# Brd_4_Sensor_Shield_Kevin_Tom.net
KiCad netlist of a schematic drawn in Altium Designer
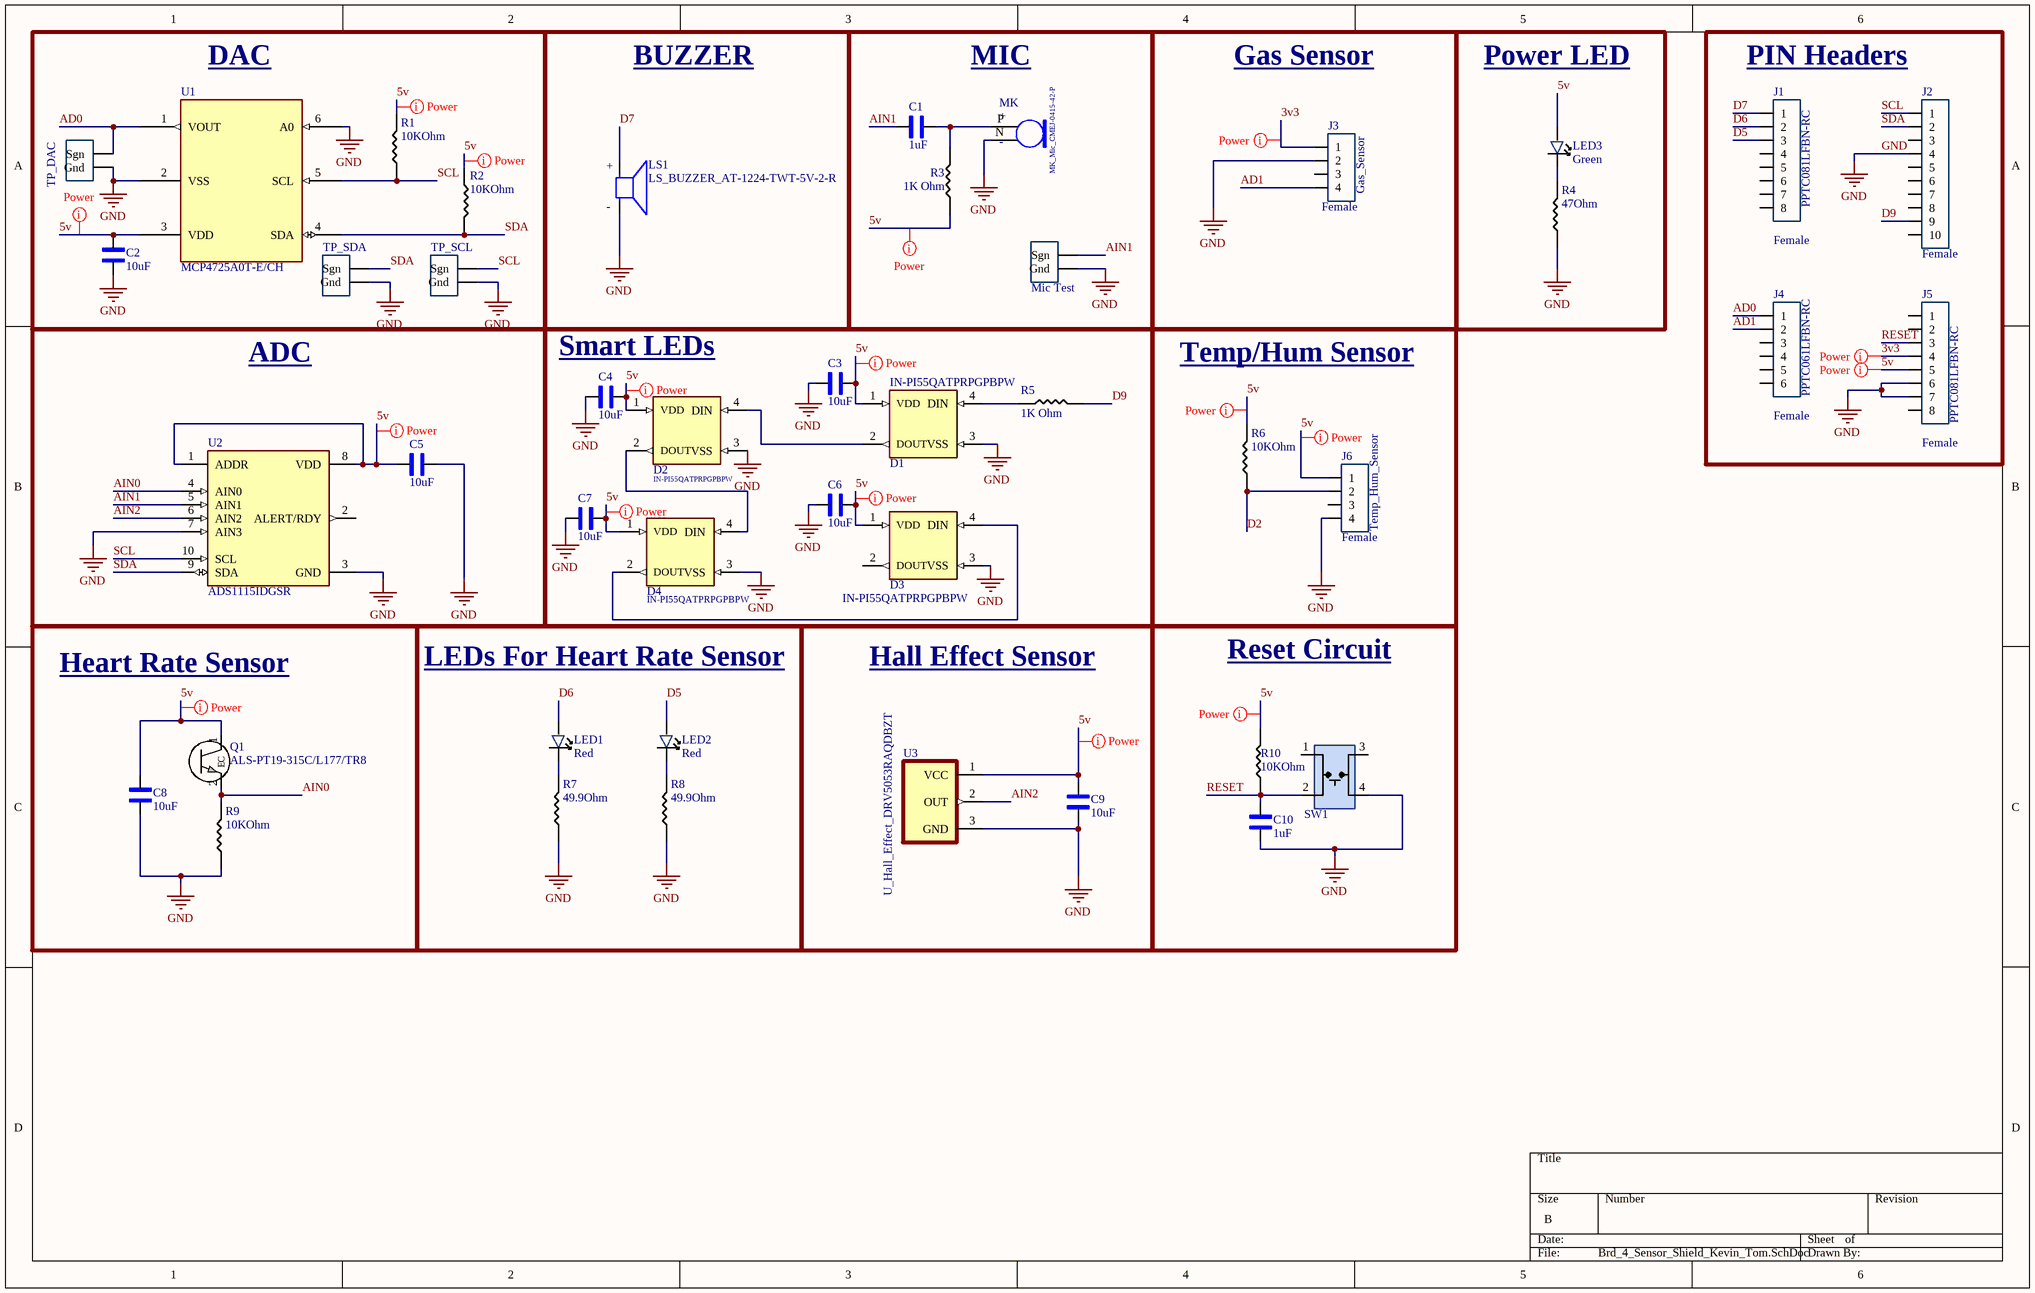
[diagram p0: Brd_4_Sensor_Shield_Kevin_Tom.SchDoc]

(export (version "E")
  (design (tool "Eeschema 10.0.6"))
  (components
    (comp (ref "C1")
      (value "1uF")
      (footprint "1206_Passive_Capacitor")
      (description "MULTILAYER CERAMIC CAPACITORS MLCC - SMD/SMT 1UF 50V 1206 ROHS")
      (fields (field (name "DIGIKEY PART") "399-8150-1-ND") (field (name "MFR PART #") "CL31B105KBHNNNE"))
      (libsource (lib "ECEN5730Lib_JLC_2021_08") (part "C_1uF_1206"))
    )
    (comp (ref "C2")
      (value "10uF")
      (footprint "1206_Passive_Capacitor")
      (description "10uF ±10% 50V X5R 1206 Multilayer Ceramic Capacitors MLCC - SMD/SMT RoHS")
      (fields (field (name "LCSC PART#") "C13585") (field (name "MFR PART #") "CL31A106KBHNNNE"))
      (libsource (lib "ECEN5730Lib_JLC_2021_08") (part "C_10uF_1206"))
    )
    (comp (ref "C3")
      (value "10uF")
      (footprint "1206_Passive_Capacitor")
      (description "10uF ±10% 50V X5R 1206 Multilayer Ceramic Capacitors MLCC - SMD/SMT RoHS")
      (fields (field (name "LCSC PART#") "C13585") (field (name "MFR PART #") "CL31A106KBHNNNE"))
      (libsource (lib "ECEN5730Lib_JLC_2021_08") (part "C_10uF_1206"))
    )
    (comp (ref "C4")
      (value "10uF")
      (footprint "1206_Passive_Capacitor")
      (description "10uF ±10% 50V X5R 1206 Multilayer Ceramic Capacitors MLCC - SMD/SMT RoHS")
      (fields (field (name "LCSC PART#") "C13585") (field (name "MFR PART #") "CL31A106KBHNNNE"))
      (libsource (lib "ECEN5730Lib_JLC_2021_08") (part "C_10uF_1206"))
    )
    (comp (ref "C5")
      (value "10uF")
      (footprint "1206_Passive_Capacitor")
      (description "10uF ±10% 50V X5R 1206 Multilayer Ceramic Capacitors MLCC - SMD/SMT RoHS")
      (fields (field (name "LCSC PART#") "C13585") (field (name "MFR PART #") "CL31A106KBHNNNE"))
      (libsource (lib "ECEN5730Lib_JLC_2021_08") (part "C_10uF_1206"))
    )
    (comp (ref "C6")
      (value "10uF")
      (footprint "1206_Passive_Capacitor")
      (description "10uF ±10% 50V X5R 1206 Multilayer Ceramic Capacitors MLCC - SMD/SMT RoHS")
      (fields (field (name "LCSC PART#") "C13585") (field (name "MFR PART #") "CL31A106KBHNNNE"))
      (libsource (lib "ECEN5730Lib_JLC_2021_08") (part "C_10uF_1206"))
    )
    (comp (ref "C7")
      (value "10uF")
      (footprint "1206_Passive_Capacitor")
      (description "10uF ±10% 50V X5R 1206 Multilayer Ceramic Capacitors MLCC - SMD/SMT RoHS")
      (fields (field (name "LCSC PART#") "C13585") (field (name "MFR PART #") "CL31A106KBHNNNE"))
      (libsource (lib "ECEN5730Lib_JLC_2021_08") (part "C_10uF_1206"))
    )
    (comp (ref "C8")
      (value "10uF")
      (footprint "1206_Passive_Capacitor")
      (description "10uF ±10% 50V X5R 1206 Multilayer Ceramic Capacitors MLCC - SMD/SMT RoHS")
      (fields (field (name "LCSC PART#") "C13585") (field (name "MFR PART #") "CL31A106KBHNNNE"))
      (libsource (lib "ECEN5730Lib_JLC_2021_08") (part "C_10uF_1206"))
    )
    (comp (ref "C9")
      (value "10uF")
      (footprint "1206_Passive_Capacitor")
      (description "10uF ±10% 50V X5R 1206 Multilayer Ceramic Capacitors MLCC - SMD/SMT RoHS")
      (fields (field (name "LCSC PART#") "C13585") (field (name "MFR PART #") "CL31A106KBHNNNE"))
      (libsource (lib "ECEN5730Lib_JLC_2021_08") (part "C_10uF_1206"))
    )
    (comp (ref "C10")
      (value "1uF")
      (footprint "1206_Passive_Capacitor")
      (description "MULTILAYER CERAMIC CAPACITORS MLCC - SMD/SMT 1UF 50V 1206 ROHS")
      (fields (field (name "DIGIKEY PART") "399-8150-1-ND") (field (name "MFR PART #") "CL31B105KBHNNNE"))
      (libsource (lib "ECEN5730Lib_JLC_2021_08") (part "C_1uF_1206"))
    )
    (comp (ref "D1")
      (value "IN-PI55QATPRPGPBPW")
      (footprint "SERIAL_LED")
      (description "Digital Series Cascade LED")
      (libsource (lib "ECEN5730Lib_Manual_2021_08") (part "LED_Smart_5050"))
    )
    (comp (ref "D2")
      (value "IN-PI55QATPRPGPBPW")
      (footprint "SERIAL_LED")
      (description "Digital Series Cascade LED")
      (libsource (lib "ECEN5730Lib_Manual_2021_08") (part "LED_Smart_5050"))
    )
    (comp (ref "D3")
      (value "IN-PI55QATPRPGPBPW")
      (footprint "SERIAL_LED")
      (description "Digital Series Cascade LED")
      (libsource (lib "ECEN5730Lib_Manual_2021_08") (part "LED_Smart_5050"))
    )
    (comp (ref "D4")
      (value "IN-PI55QATPRPGPBPW")
      (footprint "SERIAL_LED")
      (description "Digital Series Cascade LED")
      (libsource (lib "ECEN5730Lib_Manual_2021_08") (part "LED_Smart_5050"))
    )
    (comp (ref "J1")
      (value "PPTC081LFBN-RC")
      (footprint "8_PIN_ARDUINO_100MIL")
      (description "8 Position Header Connector 0.100\" (2.54mm) Through Hole Tin")
      (fields
        (field (name "DIGIKEY PART") "S7006-ND")
        (field (name "LCSC PART#") "C27438")
        (field (name "ALTIUM_VALUE") "Female")
      )
      (libsource (lib "ECEN5730Lib_JLC_2021_08") (part "JF_8_PIN_FEMALE_ARDUINO"))
    )
    (comp (ref "J2")
      (value "Female")
      (footprint "10_PIN_ARDUINO_100MIL")
      (description "10 Position Header Connector 0.100\" (2.54mm) Through Hole Tin")
      (fields (field (name "DIGIKEY PART") "S7008-ND") (field (name "LCSC PART#") "C225507"))
      (libsource (lib "ECEN5730Lib_JLC_2021_08") (part "JF_10_PIN_FEMALE_ARDUINO"))
    )
    (comp (ref "J3")
      (value "Gas_Sensor")
      (footprint "4_PIN_100MIL")
      (description "4 Position Header Connector 0.100\" (2.54mm) Through Hole Tin")
      (fields
        (field (name "DIGIKEY PART") "S7004-ND")
        (field (name "LCSC PART#") "C40877")
        (field (name "ALTIUM_VALUE") "Female")
      )
      (libsource (lib "keto_Sensor_lib_27-03") (part "JF_4_PIN_FEMALE_ARDUINO"))
    )
    (comp (ref "J4")
      (value "PPTC061LFBN-RC")
      (footprint "6_PIN_ARDUINO_100mil")
      (description "6 Position Header Connector 0.100\" (2.54mm) Through Hole Tin")
      (fields
        (field (name "DIGIKEY PART") "S7004-ND")
        (field (name "LCSC PART#") "C40877")
        (field (name "ALTIUM_VALUE") "Female")
      )
      (libsource (lib "ECEN5730Lib_JLC_2021_08") (part "JF_6_PIN_FEMALE_ARDUINO"))
    )
    (comp (ref "J5")
      (value "PPTC081LFBN-RC")
      (footprint "8_PIN_ARDUINO_100MIL")
      (description "8 Position Header Connector 0.100\" (2.54mm) Through Hole Tin")
      (fields
        (field (name "DIGIKEY PART") "S7006-ND")
        (field (name "LCSC PART#") "C27438")
        (field (name "ALTIUM_VALUE") "Female")
      )
      (libsource (lib "ECEN5730Lib_JLC_2021_08") (part "JF_8_PIN_FEMALE_ARDUINO"))
    )
    (comp (ref "J6")
      (value "Temp_Hum_Sensor")
      (footprint "4_PIN_100MIL")
      (description "4 Position Header Connector 0.100\" (2.54mm) Through Hole Tin")
      (fields
        (field (name "DIGIKEY PART") "S7004-ND")
        (field (name "LCSC PART#") "C40877")
        (field (name "ALTIUM_VALUE") "Female")
      )
      (libsource (lib "keto_Sensor_lib_27-03") (part "JF_4_PIN_FEMALE_ARDUINO"))
    )
    (comp (ref "LED1")
      (value "Red")
      (footprint "LED_1206")
      (description "Red 621~631nm 1206 Light Emitting Diodes (LED) RoHS")
      (fields (field (name "MFR PART #") "15-21/R6C-FQ1R1B/2T") (field (name "LCSC PART#") "C93133"))
      (libsource (lib "ECEN5730Lib_JLC_2021_08") (part "LED_RED_1206"))
    )
    (comp (ref "LED2")
      (value "Red")
      (footprint "LED_1206")
      (description "Red 621~631nm 1206 Light Emitting Diodes (LED) RoHS")
      (fields (field (name "MFR PART #") "15-21/R6C-FQ1R1B/2T") (field (name "LCSC PART#") "C93133"))
      (libsource (lib "ECEN5730Lib_JLC_2021_08") (part "LED_RED_1206"))
    )
    (comp (ref "LED3")
      (value "Green")
      (footprint "LED_1206")
      (description "Green 513~528nm 1206 Light Emitting Diodes (LED) RoHS")
      (fields (field (name "MFR PART #") "SZYY1206G") (field (name "LCSC PART#") "C434439"))
      (libsource (lib "ECEN5730Lib_JLC_2021_08") (part "LED_GREEN_1206"))
    )
    (comp (ref "LS1")
      (value "LS_BUZZER_AT-1224-TWT-5V-2-R")
      (footprint "XDCR_AT-1224-TWT-5V-2-R")
      (description "AUDIO TRANSDUCER 5 VP-P 87 DB 2400 HZ")
      (fields (field (name "MF") "PUI Audio,") (field (name "MP") "AT-1224-TWT-5V-2-R"))
      (libsource (lib "keto_Sensor_lib_27-03") (part "LS_BUZZER_AT-1224-TWT-5V-2-R"))
    )
    (comp (ref "Mic Test")
      (value "10x Probe TP")
      (footprint "TP10x_Probe")
      (description "Test Point 300 mil centers")
      (libsource (lib "ECEN5730Lib_Manual_2021_08") (part "TP_10x_Probe"))
    )
    (comp (ref "MK")
      (value "MK_Mic_CMEJ-0415-42-P")
      (footprint "MK_MIC_CMEJ-0415-42-P")
      (description "0.4mm OMNIDIRECTIONAL MIC")
      (fields (field (name "MF") "CUI Devices") (field (name "DIGI-KEY_PART_NUMBER") "102-6542-ND"))
      (libsource (lib "keto_Sensor_lib_27-03") (part "MK_Mic_CMEJ-0415-42-P"))
    )
    (comp (ref "Q1")
      (value "ALS-PT19-315C/L177/TR8")
      (footprint "LED_77/TR8_EVE")
      (description "Ambient Light Sensor")
      (fields (field (name "LCSC PART#") "C146233"))
      (libsource (lib "ECEN5730Lib_JLC_2021_08") (part "Q_Phototransistor"))
    )
    (comp (ref "R1")
      (value "10KOhm")
      (footprint "1206_Passive_Resitor")
      (description "10 kOhms ±5% 0.25W, 1/4W Chip Resistor 1206 (3216 Metric) Automotive AEC-Q200 Thick Film")
      (fields (field (name "DIGIKEY PART") "RMCF1206JT300RCT-ND") (field (name "LCSC PART#") "C17902"))
      (libsource (lib "ECEN5730Lib_JLC_2021_08") (part "R_10KOhm_1206"))
    )
    (comp (ref "R2")
      (value "10KOhm")
      (footprint "1206_Passive_Resitor")
      (description "10 kOhms ±5% 0.25W, 1/4W Chip Resistor 1206 (3216 Metric) Automotive AEC-Q200 Thick Film")
      (fields (field (name "DIGIKEY PART") "RMCF1206JT300RCT-ND") (field (name "LCSC PART#") "C17902"))
      (libsource (lib "ECEN5730Lib_JLC_2021_08") (part "R_10KOhm_1206"))
    )
    (comp (ref "R3")
      (value "1K Ohm")
      (footprint "1206_Passive_Resitor")
      (description "CHIP RESISTOR - SURFACE MOUNT 1KOHMS ±1% 1/4W 1206 ROHS")
      (fields (field (name "DIGIKEY PART") "RNCP1206FTD1K00CT-ND") (field (name "LCSC PART#") "C4410"))
      (libsource (lib "ECEN5730Lib_JLC_2021_08") (part "R_1K_1206"))
    )
    (comp (ref "R4")
      (value "47Ohm")
      (footprint "1206_Passive_Resitor")
      (description "47Ω ±5% 0.25W ±200ppm/℃ 1206 Chip Resistor - Surface Mount RoHS")
      (fields (field (name "MFR PART #") "1206W4J0470T5E") (field (name "LCSC PART#") "C25384"))
      (libsource (lib "ECEN5730Lib_JLC_2021_08") (part "R_47Ohm_1206"))
    )
    (comp (ref "R5")
      (value "1K Ohm")
      (footprint "1206_Passive_Resitor")
      (description "CHIP RESISTOR - SURFACE MOUNT 1KOHMS ±1% 1/4W 1206 ROHS")
      (fields (field (name "DIGIKEY PART") "RNCP1206FTD1K00CT-ND") (field (name "LCSC PART#") "C4410"))
      (libsource (lib "ECEN5730Lib_JLC_2021_08") (part "R_1K_1206"))
    )
    (comp (ref "R6")
      (value "10KOhm")
      (footprint "1206_Passive_Resitor")
      (description "10 kOhms ±5% 0.25W, 1/4W Chip Resistor 1206 (3216 Metric) Automotive AEC-Q200 Thick Film")
      (fields (field (name "DIGIKEY PART") "RMCF1206JT300RCT-ND") (field (name "LCSC PART#") "C17902"))
      (libsource (lib "ECEN5730Lib_JLC_2021_08") (part "R_10KOhm_1206"))
    )
    (comp (ref "R7")
      (value "49.9Ohm")
      (footprint "0402_Passive_Resistor")
      (description "CHIP RESISTOR - SURFACE MOUNT 49.9OHMS ±1% 1/16W 0402 ROHS")
      (fields (field (name "MFR PART #") "0402WGF499JTCE") (field (name "LCSC PART#") "C25120"))
      (libsource (lib "ECEN5730Lib_JLC_2021_08") (part "R_50Ohm_0402"))
    )
    (comp (ref "R8")
      (value "49.9Ohm")
      (footprint "0402_Passive_Resistor")
      (description "CHIP RESISTOR - SURFACE MOUNT 49.9OHMS ±1% 1/16W 0402 ROHS")
      (fields (field (name "MFR PART #") "0402WGF499JTCE") (field (name "LCSC PART#") "C25120"))
      (libsource (lib "ECEN5730Lib_JLC_2021_08") (part "R_50Ohm_0402"))
    )
    (comp (ref "R9")
      (value "10KOhm")
      (footprint "1206_Passive_Resitor")
      (description "10 kOhms ±5% 0.25W, 1/4W Chip Resistor 1206 (3216 Metric) Automotive AEC-Q200 Thick Film")
      (fields (field (name "DIGIKEY PART") "RMCF1206JT300RCT-ND") (field (name "LCSC PART#") "C17902"))
      (libsource (lib "ECEN5730Lib_JLC_2021_08") (part "R_10KOhm_1206"))
    )
    (comp (ref "R10")
      (value "10KOhm")
      (footprint "1206_Passive_Resitor")
      (description "10 kOhms ±5% 0.25W, 1/4W Chip Resistor 1206 (3216 Metric) Automotive AEC-Q200 Thick Film")
      (fields (field (name "DIGIKEY PART") "RMCF1206JT300RCT-ND") (field (name "LCSC PART#") "C17902"))
      (libsource (lib "ECEN5730Lib_JLC_2021_08") (part "R_10KOhm_1206"))
    )
    (comp (ref "SW1")
      (value "TL3305AF160QG")
      (footprint "Switch_JLC")
      (description "Tactile Switch SPST-NO Top Actuated Surface Mount")
      (fields (field (name "MFR PART #") "C174049"))
      (libsource (lib "ECEN5730Lib_JLC_2021_08") (part "SW_Push_Button_JLC"))
    )
    (comp (ref "TP2")
      (value "TP_DAC")
      (footprint "TP10x_Probe")
      (description "Test Point 300 mil centers")
      (libsource (lib "ECEN5730Lib_Manual_2021_08") (part "TP_10x_Probe"))
    )
    (comp (ref "TP3")
      (value "TP_SDA")
      (footprint "TP10x_Probe")
      (description "Test Point 300 mil centers")
      (libsource (lib "ECEN5730Lib_Manual_2021_08") (part "TP_10x_Probe"))
    )
    (comp (ref "TP4")
      (value "TP_SCL")
      (footprint "TP10x_Probe")
      (description "Test Point 300 mil centers")
      (libsource (lib "ECEN5730Lib_Manual_2021_08") (part "TP_10x_Probe"))
    )
    (comp (ref "U1")
      (value "MCP4725A0T-E/CH")
      (footprint "DAC_MCP4725A0T-E/CH")
      (description "Voltage-Buffered 12 1 I2C SOT-23-6 Digital To Analog Converters (DACs) ROHS")
      (fields (field (name "LCSC PART#") "C144198"))
      (libsource (lib "keto_Sensor_lib_27-03") (part "U_DAC_MCP4725A0T-E/CH"))
    )
    (comp (ref "U2")
      (value "ADS1115IDGSR")
      (footprint "ADC_ADS1115IDGSR")
      (description "16-Bit ADC with Integrated MUX, PGA, Comparator, Oscillator, and Reference 10-VSSOP -40 to 125")
      (fields (field (name "LCSC PART#") "C37593"))
      (libsource (lib "ECEN5730Lib_JLC_2021_08") (part "U_ADC_ADS1115IDGSR"))
    )
    (comp (ref "U3")
      (value "U_Hall_Effect_DRV5053RAQDBZT")
      (footprint "U_Hall_Effect_SOT95P237X112-3N")
      (description "SENSOR LINEAR ANALOG SOT23-3")
      (fields (field (name "MFR PART #") "DRV5053RAQDBZT"))
      (libsource (lib "keto_Sensor_lib_27-03") (part "U_Hall_Effect_DRV5053RAQDBZT"))
    )
  )
  (nets
    (net (code "1") (name "/3v3") (class "Default")
      (node (ref "J3") (pin "1") (pinfunction "1_1") (pintype "passive"))
      (node (ref "J5") (pin "4") (pinfunction "4_4") (pintype "passive"))
    )
    (net (code "2") (name "/5v") (class "Default")
      (node (ref "C2") (pin "2") (pinfunction "2_2") (pintype "passive"))
      (node (ref "C3") (pin "1") (pinfunction "1_1") (pintype "passive"))
      (node (ref "C4") (pin "1") (pinfunction "1_1") (pintype "passive"))
      (node (ref "C5") (pin "2") (pinfunction "2_2") (pintype "passive"))
      (node (ref "C6") (pin "1") (pinfunction "1_1") (pintype "passive"))
      (node (ref "C7") (pin "1") (pinfunction "1_1") (pintype "passive"))
      (node (ref "C8") (pin "1") (pinfunction "1_1") (pintype "passive"))
      (node (ref "C9") (pin "1") (pinfunction "1_1") (pintype "passive"))
      (node (ref "D1") (pin "1") (pinfunction "VDD_1") (pintype "input"))
      (node (ref "D2") (pin "1") (pinfunction "VDD_1") (pintype "input"))
      (node (ref "D3") (pin "1") (pinfunction "VDD_1") (pintype "input"))
      (node (ref "D4") (pin "1") (pinfunction "VDD_1") (pintype "input"))
      (node (ref "J5") (pin "5") (pinfunction "5_5") (pintype "passive"))
      (node (ref "J6") (pin "1") (pinfunction "1_1") (pintype "passive"))
      (node (ref "LED3") (pin "1") (pinfunction "1_1") (pintype "passive"))
      (node (ref "Q1") (pin "1") (pinfunction "C_1") (pintype "passive"))
      (node (ref "R1") (pin "2") (pinfunction "2_2") (pintype "passive"))
      (node (ref "R10") (pin "2") (pinfunction "2_2") (pintype "passive"))
      (node (ref "R2") (pin "1") (pinfunction "1_1") (pintype "passive"))
      (node (ref "R3") (pin "1") (pinfunction "1_1") (pintype "passive"))
      (node (ref "R6") (pin "2") (pinfunction "2_2") (pintype "passive"))
      (node (ref "U1") (pin "3") (pinfunction "VDD_3") (pintype "power_in"))
      (node (ref "U2") (pin "1") (pinfunction "ADDR_1") (pintype "passive"))
      (node (ref "U2") (pin "8") (pinfunction "VDD_8") (pintype "power_in"))
      (node (ref "U3") (pin "1") (pinfunction "VCC_1") (pintype "power_in"))
    )
    (net (code "3") (name "/AD0") (class "Default")
      (node (ref "J4") (pin "1") (pinfunction "1_1") (pintype "passive"))
      (node (ref "TP2") (pin "1") (pinfunction "Sgn_1") (pintype "passive"))
      (node (ref "U1") (pin "1") (pinfunction "VOUT_1") (pintype "output"))
    )
    (net (code "4") (name "/AD1") (class "Default")
      (node (ref "J3") (pin "4") (pinfunction "4_4") (pintype "passive"))
      (node (ref "J4") (pin "2") (pinfunction "2_2") (pintype "passive"))
    )
    (net (code "5") (name "/AIN0") (class "Default")
      (node (ref "Q1") (pin "2") (pinfunction "E_2") (pintype "passive"))
      (node (ref "R9") (pin "2") (pinfunction "2_2") (pintype "passive"))
      (node (ref "U2") (pin "4") (pinfunction "AIN0_4") (pintype "input"))
    )
    (net (code "6") (name "/AIN1") (class "Default")
      (node (ref "C1") (pin "1") (pinfunction "1_1") (pintype "passive"))
      (node (ref "Mic Test") (pin "1") (pinfunction "Sgn_1") (pintype "passive"))
      (node (ref "U2") (pin "5") (pinfunction "AIN1_5") (pintype "input"))
    )
    (net (code "7") (name "/AIN2") (class "Default")
      (node (ref "U2") (pin "6") (pinfunction "AIN2_6") (pintype "input"))
      (node (ref "U3") (pin "2") (pinfunction "OUT_2") (pintype "output"))
    )
    (net (code "8") (name "/D2") (class "Default")
      (node (ref "J6") (pin "2") (pinfunction "2_2") (pintype "passive"))
      (node (ref "R6") (pin "1") (pinfunction "1_1") (pintype "passive"))
    )
    (net (code "9") (name "/D5") (class "Default")
      (node (ref "J1") (pin "3") (pinfunction "3_3") (pintype "passive"))
      (node (ref "LED2") (pin "1") (pinfunction "1_1") (pintype "passive"))
    )
    (net (code "10") (name "/D6") (class "Default")
      (node (ref "J1") (pin "2") (pinfunction "2_2") (pintype "passive"))
      (node (ref "LED1") (pin "1") (pinfunction "1_1") (pintype "passive"))
    )
    (net (code "11") (name "/D7") (class "Default")
      (node (ref "J1") (pin "1") (pinfunction "1_1") (pintype "passive"))
      (node (ref "LS1") (pin "P") (pinfunction "P_P") (pintype "passive"))
    )
    (net (code "12") (name "/D9") (class "Default")
      (node (ref "J2") (pin "9") (pinfunction "9_9") (pintype "passive"))
      (node (ref "R5") (pin "2") (pinfunction "2_2") (pintype "passive"))
    )
    (net (code "13") (name "/RESET") (class "Default")
      (node (ref "C10") (pin "2") (pinfunction "2_2") (pintype "passive"))
      (node (ref "J5") (pin "3") (pinfunction "3_3") (pintype "passive"))
      (node (ref "R10") (pin "1") (pinfunction "1_1") (pintype "passive"))
      (node (ref "SW1") (pin "2") (pinfunction "2_2") (pintype "passive"))
    )
    (net (code "14") (name "/SCL") (class "Default")
      (node (ref "J2") (pin "1") (pinfunction "1_1") (pintype "passive"))
      (node (ref "R1") (pin "1") (pinfunction "1_1") (pintype "passive"))
      (node (ref "TP4") (pin "1") (pinfunction "Sgn_1") (pintype "passive"))
      (node (ref "U1") (pin "5") (pinfunction "SCL_5") (pintype "input"))
      (node (ref "U2") (pin "10") (pinfunction "SCL_10") (pintype "input"))
    )
    (net (code "15") (name "/SDA") (class "Default")
      (node (ref "J2") (pin "2") (pinfunction "2_2") (pintype "passive"))
      (node (ref "R2") (pin "2") (pinfunction "2_2") (pintype "passive"))
      (node (ref "TP3") (pin "1") (pinfunction "Sgn_1") (pintype "passive"))
      (node (ref "U1") (pin "4") (pinfunction "SDA_4") (pintype "bidirectional"))
      (node (ref "U2") (pin "9") (pinfunction "SDA_9") (pintype "bidirectional"))
    )
    (net (code "16") (name "GND") (class "Default")
      (node (ref "C10") (pin "1") (pinfunction "1_1") (pintype "passive"))
      (node (ref "C2") (pin "1") (pinfunction "1_1") (pintype "passive"))
      (node (ref "C3") (pin "2") (pinfunction "2_2") (pintype "passive"))
      (node (ref "C4") (pin "2") (pinfunction "2_2") (pintype "passive"))
      (node (ref "C5") (pin "1") (pinfunction "1_1") (pintype "passive"))
      (node (ref "C6") (pin "2") (pinfunction "2_2") (pintype "passive"))
      (node (ref "C7") (pin "2") (pinfunction "2_2") (pintype "passive"))
      (node (ref "C8") (pin "2") (pinfunction "2_2") (pintype "passive"))
      (node (ref "C9") (pin "2") (pinfunction "2_2") (pintype "passive"))
      (node (ref "D1") (pin "3") (pinfunction "VSS_3") (pintype "input"))
      (node (ref "D2") (pin "3") (pinfunction "VSS_3") (pintype "input"))
      (node (ref "D3") (pin "3") (pinfunction "VSS_3") (pintype "input"))
      (node (ref "D4") (pin "3") (pinfunction "VSS_3") (pintype "input"))
      (node (ref "J2") (pin "4") (pinfunction "4_4") (pintype "passive"))
      (node (ref "J3") (pin "2") (pinfunction "2_2") (pintype "passive"))
      (node (ref "J5") (pin "6") (pinfunction "6_6") (pintype "passive"))
      (node (ref "J5") (pin "7") (pinfunction "7_7") (pintype "passive"))
      (node (ref "J6") (pin "4") (pinfunction "4_4") (pintype "passive"))
      (node (ref "LS1") (pin "N") (pinfunction "N_N") (pintype "passive"))
      (node (ref "MK") (pin "N") (pinfunction "GND_N") (pintype "passive"))
      (node (ref "Mic Test") (pin "2") (pinfunction "Gnd_2") (pintype "passive"))
      (node (ref "R4") (pin "1") (pinfunction "1_1") (pintype "passive"))
      (node (ref "R7") (pin "1") (pinfunction "1_1") (pintype "passive"))
      (node (ref "R8") (pin "1") (pinfunction "1_1") (pintype "passive"))
      (node (ref "R9") (pin "1") (pinfunction "1_1") (pintype "passive"))
      (node (ref "SW1") (pin "4") (pinfunction "4_4") (pintype "passive"))
      (node (ref "TP2") (pin "2") (pinfunction "Gnd_2") (pintype "passive"))
      (node (ref "TP3") (pin "2") (pinfunction "Gnd_2") (pintype "passive"))
      (node (ref "TP4") (pin "2") (pinfunction "Gnd_2") (pintype "passive"))
      (node (ref "U1") (pin "2") (pinfunction "VSS_2") (pintype "power_in"))
      (node (ref "U1") (pin "6") (pinfunction "A0_6") (pintype "input"))
      (node (ref "U2") (pin "3") (pinfunction "GND_3") (pintype "power_in"))
      (node (ref "U2") (pin "7") (pinfunction "AIN3_7") (pintype "input"))
      (node (ref "U3") (pin "3") (pinfunction "GND_3") (pintype "power_in"))
    )
    (net (code "17") (name "Net-(D1-DIN)") (class "Default")
      (node (ref "D1") (pin "4") (pinfunction "DIN_4") (pintype "input"))
      (node (ref "R5") (pin "1") (pinfunction "1_1") (pintype "passive"))
    )
    (net (code "18") (name "Net-(D1-DOUT)") (class "Default")
      (node (ref "D1") (pin "2") (pinfunction "DOUT_2") (pintype "output"))
      (node (ref "D2") (pin "4") (pinfunction "DIN_4") (pintype "input"))
    )
    (net (code "19") (name "Net-(D2-DOUT)") (class "Default")
      (node (ref "D2") (pin "2") (pinfunction "DOUT_2") (pintype "output"))
      (node (ref "D4") (pin "4") (pinfunction "DIN_4") (pintype "input"))
    )
    (net (code "20") (name "Net-(D3-DIN)") (class "Default")
      (node (ref "D3") (pin "4") (pinfunction "DIN_4") (pintype "input"))
      (node (ref "D4") (pin "2") (pinfunction "DOUT_2") (pintype "output"))
    )
    (net (code "21") (name "Net-(LED1-Pad2)") (class "Default")
      (node (ref "LED1") (pin "2") (pinfunction "2_2") (pintype "passive"))
      (node (ref "R7") (pin "2") (pinfunction "2_2") (pintype "passive"))
    )
    (net (code "22") (name "Net-(LED2-Pad2)") (class "Default")
      (node (ref "LED2") (pin "2") (pinfunction "2_2") (pintype "passive"))
      (node (ref "R8") (pin "2") (pinfunction "2_2") (pintype "passive"))
    )
    (net (code "23") (name "Net-(LED3-Pad2)") (class "Default")
      (node (ref "LED3") (pin "2") (pinfunction "2_2") (pintype "passive"))
      (node (ref "R4") (pin "2") (pinfunction "2_2") (pintype "passive"))
    )
    (net (code "24") (name "Net-(MK-OUTPUT)") (class "Default")
      (node (ref "C1") (pin "2") (pinfunction "2_2") (pintype "passive"))
      (node (ref "MK") (pin "P") (pinfunction "OUTPUT_P") (pintype "passive"))
      (node (ref "R3") (pin "2") (pinfunction "2_2") (pintype "passive"))
    )
    (net (code "25") (name "unconnected-(D3-DOUT-Pad2)") (class "Default")
      (node (ref "D3") (pin "2") (pinfunction "DOUT_2") (pintype "output"))
    )
    (net (code "26") (name "unconnected-(J1-Pad4)") (class "Default")
      (node (ref "J1") (pin "4") (pinfunction "4_4") (pintype "passive"))
    )
    (net (code "27") (name "unconnected-(J1-Pad5)") (class "Default")
      (node (ref "J1") (pin "5") (pinfunction "5_5") (pintype "passive"))
    )
    (net (code "28") (name "unconnected-(J1-Pad6)") (class "Default")
      (node (ref "J1") (pin "6") (pinfunction "6_6") (pintype "passive"))
    )
    (net (code "29") (name "unconnected-(J1-Pad7)") (class "Default")
      (node (ref "J1") (pin "7") (pinfunction "7_7") (pintype "passive"))
    )
    (net (code "30") (name "unconnected-(J1-Pad8)") (class "Default")
      (node (ref "J1") (pin "8") (pinfunction "8_8") (pintype "passive"))
    )
    (net (code "31") (name "unconnected-(J2-Pad3)") (class "Default")
      (node (ref "J2") (pin "3") (pinfunction "3_3") (pintype "passive"))
    )
    (net (code "32") (name "unconnected-(J2-Pad5)") (class "Default")
      (node (ref "J2") (pin "5") (pinfunction "5_5") (pintype "passive"))
    )
    (net (code "33") (name "unconnected-(J2-Pad6)") (class "Default")
      (node (ref "J2") (pin "6") (pinfunction "6_6") (pintype "passive"))
    )
    (net (code "34") (name "unconnected-(J2-Pad7)") (class "Default")
      (node (ref "J2") (pin "7") (pinfunction "7_7") (pintype "passive"))
    )
    (net (code "35") (name "unconnected-(J2-Pad8)") (class "Default")
      (node (ref "J2") (pin "8") (pinfunction "8_8") (pintype "passive"))
    )
    (net (code "36") (name "unconnected-(J2-Pad10)") (class "Default")
      (node (ref "J2") (pin "10") (pinfunction "10_10") (pintype "passive"))
    )
    (net (code "37") (name "unconnected-(J3-Pad3)") (class "Default")
      (node (ref "J3") (pin "3") (pinfunction "3_3") (pintype "passive"))
    )
    (net (code "38") (name "unconnected-(J4-Pad3)") (class "Default")
      (node (ref "J4") (pin "3") (pinfunction "3_3") (pintype "passive"))
    )
    (net (code "39") (name "unconnected-(J4-Pad4)") (class "Default")
      (node (ref "J4") (pin "4") (pinfunction "4_4") (pintype "passive"))
    )
    (net (code "40") (name "unconnected-(J4-Pad5)") (class "Default")
      (node (ref "J4") (pin "5") (pinfunction "5_5") (pintype "passive"))
    )
    (net (code "41") (name "unconnected-(J4-Pad6)") (class "Default")
      (node (ref "J4") (pin "6") (pinfunction "6_6") (pintype "passive"))
    )
    (net (code "42") (name "unconnected-(J5-Pad1)") (class "Default")
      (node (ref "J5") (pin "1") (pinfunction "1_1") (pintype "passive"))
    )
    (net (code "43") (name "unconnected-(J5-Pad2)") (class "Default")
      (node (ref "J5") (pin "2") (pinfunction "2_2") (pintype "passive"))
    )
    (net (code "44") (name "unconnected-(J5-Pad8)") (class "Default")
      (node (ref "J5") (pin "8") (pinfunction "8_8") (pintype "passive"))
    )
    (net (code "45") (name "unconnected-(J6-Pad3)") (class "Default")
      (node (ref "J6") (pin "3") (pinfunction "3_3") (pintype "passive"))
    )
    (net (code "46") (name "unconnected-(SW1-Pad1)") (class "Default")
      (node (ref "SW1") (pin "1") (pinfunction "1_1") (pintype "passive"))
    )
    (net (code "47") (name "unconnected-(SW1-Pad3)") (class "Default")
      (node (ref "SW1") (pin "3") (pinfunction "3_3") (pintype "passive"))
    )
    (net (code "48") (name "unconnected-(U2-ALERT{slash}RDY-Pad2)") (class "Default")
      (node (ref "U2") (pin "2") (pinfunction "ALERT/RDY_2") (pintype "output"))
    )
  )
)
